# MB1280.net
KiCad netlist of a schematic drawn in Altium Designer
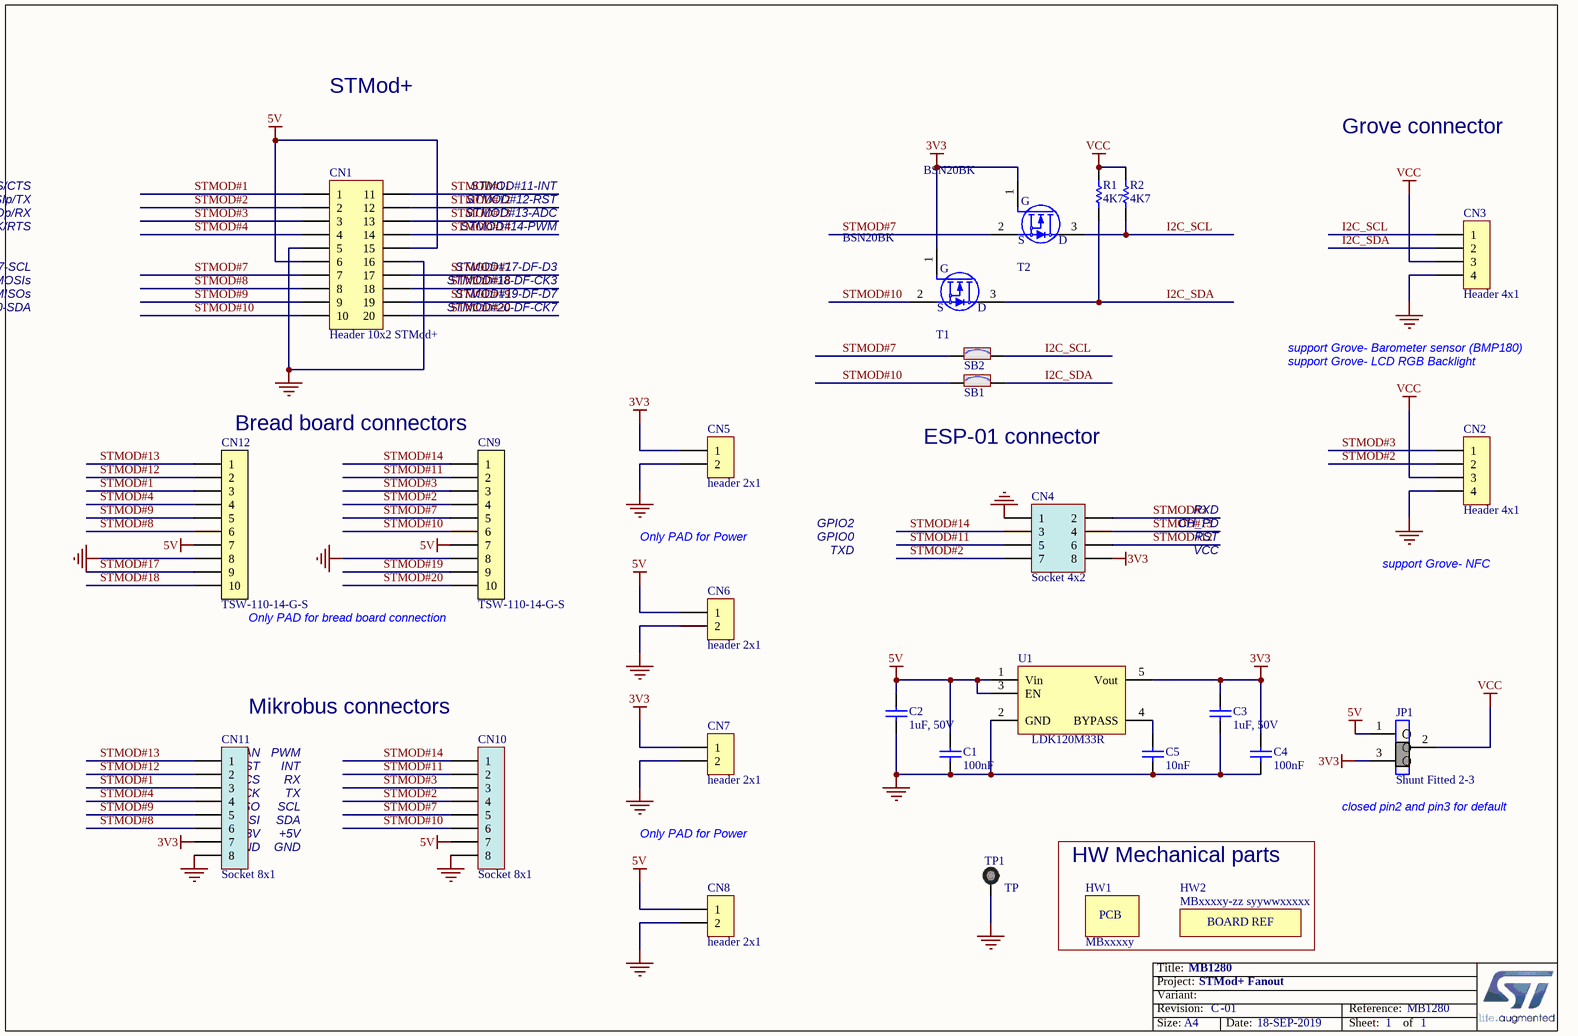
[diagram p0: MB1280.SchDoc]

(export (version "E")
  (design (tool "Eeschema 10.0.6"))
  (components
    (comp (ref "C1")
      (value "100nF")
      (footprint "C0603")
      (description "Capacitor, MLCC, 100nF, 16V, X7R, 10%, 0603, T=0,8mm")
      (fields
        (field (name "INTERNAL_PART_NUMBER") "MCD-00211")
        (field (name "MANUFACTURER_PART_NUMBER") "CC0603KRX7R7BB104")
        (field (name "PROVIDED_BY") "SUBCO")
      )
      (libsource (lib "MCD_PARTS_database") (part "Capacitor"))
    )
    (comp (ref "C2")
      (value "1uF, 50V")
      (footprint "C0603_H0P8")
      (description "Capacitor,1uF,50V,X5R,10%,0603, T=0.8mm")
      (fields
        (field (name "INTERNAL_PART_NUMBER") "MCD-01703")
        (field (name "MANUFACTURER_PART_NUMBER") "CC0603KRX5R9BB105")
        (field (name "PROVIDED_BY") "SUBCO")
      )
      (libsource (lib "MCD_PARTS_database") (part "Capacitor"))
    )
    (comp (ref "C3")
      (value "1uF, 50V")
      (footprint "C0603_H0P8")
      (description "Capacitor,1uF,50V,X5R,10%,0603, T=0.8mm")
      (fields
        (field (name "INTERNAL_PART_NUMBER") "MCD-01703")
        (field (name "MANUFACTURER_PART_NUMBER") "CC0603KRX5R9BB105")
        (field (name "PROVIDED_BY") "SUBCO")
      )
      (libsource (lib "MCD_PARTS_database") (part "Capacitor"))
    )
    (comp (ref "C4")
      (value "100nF")
      (footprint "C0603")
      (description "Capacitor, MLCC, 100nF, 16V, X7R, 10%, 0603, T=0,8mm")
      (fields
        (field (name "INTERNAL_PART_NUMBER") "MCD-00211")
        (field (name "MANUFACTURER_PART_NUMBER") "CC0603KRX7R7BB104")
        (field (name "PROVIDED_BY") "SUBCO")
      )
      (libsource (lib "MCD_PARTS_database") (part "Capacitor"))
    )
    (comp (ref "C5")
      (value "10nF")
      (footprint "C0603")
      (description "Capacitor, MLCC, 10nF, 50V, X7R, 10%, 0603, T=0.8mm")
      (fields
        (field (name "INTERNAL_PART_NUMBER") "MCD-00017")
        (field (name "MANUFACTURER_PART_NUMBER") "CC0603KRX7R9BB103")
        (field (name "PROVIDED_BY") "SUBCO")
      )
      (libsource (lib "MCD_PARTS_database") (part "Capacitor"))
    )
    (comp (ref "CN1")
      (value "Header 10x2 STMod+")
      (footprint "CON_SAMTEC_TMM-110-01-L-D-RA__STMOD+")
      (description "Header 10x2, 2mm, RA, TH, Height 3.20mm/3.50mm")
      (fields
        (field (name "INTERNAL_PART_NUMBER") "MCD-00288")
        (field (name "MANUFACTURER_PART_NUMBER") "TMM-110-01-L-D-RA")
        (field (name "PROVIDED_BY") "SUBCO")
      )
      (libsource (lib "MCD_PARTS_database") (part "Header 10x2 STMod+"))
    )
    (comp (ref "CN2")
      (value "Header 4x1")
      (footprint "CON_988-JIUBABA_A2006LF-04A")
      (description "Header 4x1, 2mm, VR, SMT")
      (fields
        (field (name "INTERNAL_PART_NUMBER") "MCD-01741")
        (field (name "MANUFACTURER_PART_NUMBER") "A2006LF-04A")
        (field (name "PROVIDED_BY") "SUBCO")
      )
      (libsource (lib "MCD_PARTS_database") (part "Header 4x1"))
    )
    (comp (ref "CN3")
      (value "Header 4x1")
      (footprint "CON_988-JIUBABA_A2006LF-04A")
      (description "Header 4x1, 2mm, VR, SMT")
      (fields
        (field (name "INTERNAL_PART_NUMBER") "MCD-01741")
        (field (name "MANUFACTURER_PART_NUMBER") "A2006LF-04A")
        (field (name "PROVIDED_BY") "SUBCO")
      )
      (libsource (lib "MCD_PARTS_database") (part "Header 4x1"))
    )
    (comp (ref "CN4")
      (value "Socket 4x2")
      (footprint "CON_SAMTEC_SSW-104-01-X-D")
      (description "Socket 4x2,2.54mm,VR,TH, height 8.51/2.64mm")
      (fields
        (field (name "INTERNAL_PART_NUMBER") "MCD-01742")
        (field (name "MANUFACTURER_PART_NUMBER") "SSW-104-01-G-D")
        (field (name "PROVIDED_BY") "SUBCO")
      )
      (libsource (lib "MCD_PARTS_database") (part "Socket 4x2"))
    )
    (comp (ref "CN5")
      (value "header 2x1")
      (footprint "CON_988-JIUBABA_PHFS25-11-02-G0B115-T-1")
      (description "Header, 2x1, 2.54mm, VR, TH, Height 6mm/3mm")
      (fields
        (field (name "INTERNAL_PART_NUMBER") "MCD-00314")
        (field (name "MANUFACTURER_PART_NUMBER") "PHFS25-11-02-G0B115-T-1")
        (field (name "PROVIDED_BY") "SUBCO")
      )
      (libsource (lib "MCD_PARTS_database") (part "Header 2x1"))
    )
    (comp (ref "CN6")
      (value "header 2x1")
      (footprint "CON_988-JIUBABA_PHFS25-11-02-G0B115-T-1")
      (description "Header, 2x1, 2.54mm, VR, TH, Height 6mm/3mm")
      (fields
        (field (name "INTERNAL_PART_NUMBER") "MCD-00314")
        (field (name "MANUFACTURER_PART_NUMBER") "PHFS25-11-02-G0B115-T-1")
        (field (name "PROVIDED_BY") "SUBCO")
      )
      (libsource (lib "MCD_PARTS_database") (part "Header 2x1"))
    )
    (comp (ref "CN7")
      (value "header 2x1")
      (footprint "CON_988-JIUBABA_PHFS25-11-02-G0B115-T-1")
      (description "Header, 2x1, 2.54mm, VR, TH, Height 6mm/3mm")
      (fields
        (field (name "INTERNAL_PART_NUMBER") "MCD-00314")
        (field (name "MANUFACTURER_PART_NUMBER") "PHFS25-11-02-G0B115-T-1")
        (field (name "PROVIDED_BY") "SUBCO")
      )
      (libsource (lib "MCD_PARTS_database") (part "Header 2x1"))
    )
    (comp (ref "CN8")
      (value "header 2x1")
      (footprint "CON_988-JIUBABA_PHFS25-11-02-G0B115-T-1")
      (description "Header, 2x1, 2.54mm, VR, TH, Height 6mm/3mm")
      (fields
        (field (name "INTERNAL_PART_NUMBER") "MCD-00314")
        (field (name "MANUFACTURER_PART_NUMBER") "PHFS25-11-02-G0B115-T-1")
        (field (name "PROVIDED_BY") "SUBCO")
      )
      (libsource (lib "MCD_PARTS_database") (part "Header 2x1"))
    )
    (comp (ref "CN9")
      (value "TSW-110-14-G-S")
      (footprint "CON_SAMTEC_TSW-110-14-G-S")
      (description "Header 10x1, 2,54mm height  10.67mm")
      (fields
        (field (name "INTERNAL_PART_NUMBER") "MCD-01591")
        (field (name "MANUFACTURER") "SAMTEC")
        (field (name "PROVIDED_BY") "SUBCO")
      )
      (libsource (lib "MCD_PARTS_database") (part "Header 10x1"))
    )
    (comp (ref "CN10")
      (value "Socket 8x1")
      (footprint "CON_SAMTEC_SSW-108-01-X-S")
      (description "Socket 8x1, 2.54mm, VR, TH, height 8.51/2.64mm")
      (fields
        (field (name "INTERNAL_PART_NUMBER") "MCD-01743")
        (field (name "MANUFACTURER_PART_NUMBER") "SSW-108-01-x-S")
        (field (name "PROVIDED_BY") "SUBCO")
      )
      (libsource (lib "MCD_PARTS_database") (part "Socket 8x1"))
    )
    (comp (ref "CN11")
      (value "Socket 8x1")
      (footprint "CON_SAMTEC_SSW-108-01-X-S")
      (description "Socket 8x1, 2.54mm, VR, TH, height 8.51/2.64mm")
      (fields
        (field (name "INTERNAL_PART_NUMBER") "MCD-01743")
        (field (name "MANUFACTURER_PART_NUMBER") "SSW-108-01-x-S")
        (field (name "PROVIDED_BY") "SUBCO")
      )
      (libsource (lib "MCD_PARTS_database") (part "Socket 8x1"))
    )
    (comp (ref "CN12")
      (value "TSW-110-14-G-S")
      (footprint "CON_SAMTEC_TSW-110-14-G-S")
      (description "Header 10x1, 2,54mm height  10.67mm")
      (fields
        (field (name "INTERNAL_PART_NUMBER") "MCD-01591")
        (field (name "MANUFACTURER") "SAMTEC")
        (field (name "PROVIDED_BY") "SUBCO")
      )
      (libsource (lib "MCD_PARTS_database") (part "Header 10x1"))
    )
    (comp (ref "HW1")
      (value "MBxxxxy")
      (description "PCB, xxxx for PCB number, Y for PCB revision")
      (fields
        (field (name "INTERNAL_PART_NUMBER") "MCD-00216")
        (field (name "MANUFACTURER_PART_NUMBER") "n/a")
        (field (name "PROVIDED_BY") "SUBCO")
      )
      (libsource (lib "MCD_PARTS_database") (part "PCB"))
    )
    (comp (ref "HW2")
      (value "MBxxxxy-zz syywwxxxxx")
      (footprint "STICKER_25X9")
      (description "Sticker to mention board reference + serial number")
      (fields
        (field (name "INTERNAL_PART_NUMBER") "MCD-00235")
        (field (name "MANUFACTURER_PART_NUMBER") "n/a")
        (field (name "PROVIDED_BY") "SUBCO")
      )
      (libsource (lib "MCD_PARTS_database") (part "STICKER_BOARD_REF"))
    )
    (comp (ref "JP1")
      (value "Shunt Fitted 2-3")
      (footprint "CON_SAMTEC_TSW-103-07-F-S")
      (description "Header, 3x1, 2,54mm, VR, TH, Height 5.84mm/2.54mm - Shunt Fitted 2-3 by default")
      (fields
        (field (name "INTERNAL_PART_NUMBER") "MCD-00685")
        (field (name "MANUFACTURER_PART_NUMBER") "TSW-103-07-F-S")
        (field (name "PROVIDED_BY") "SUBCO")
      )
      (libsource (lib "MCD_PARTS_database") (part "Jumper_Header 3x1 Fitted 2-3"))
    )
    (comp (ref "R1")
      (value "4K7")
      (footprint "R0603")
      (description "Resistor,4K7,0603,1%,1/10W")
      (fields
        (field (name "INTERNAL_PART_NUMBER") "MCD-00219")
        (field (name "MANUFACTURER_PART_NUMBER") "RC0603FR-074K7L")
        (field (name "PROVIDED_BY") "SUBCO")
      )
      (libsource (lib "MCD_PARTS_database") (part "Resistor"))
    )
    (comp (ref "R2")
      (value "4K7")
      (footprint "R0603")
      (description "Resistor,4K7,0603,1%,1/10W")
      (fields
        (field (name "INTERNAL_PART_NUMBER") "MCD-00219")
        (field (name "MANUFACTURER_PART_NUMBER") "RC0603FR-074K7L")
        (field (name "PROVIDED_BY") "SUBCO")
      )
      (libsource (lib "MCD_PARTS_database") (part "Resistor"))
    )
    (comp (ref "SB1")
      (value "SB_ON")
      (footprint "SOLDER-BRIDGE_R0603-0R")
      (description "Solder Bridge ON")
      (fields
        (field (name "INTERNAL_PART_NUMBER") "MCD-00071")
        (field (name "MANUFACTURER_PART_NUMBER") "RC0603JR-070RL")
        (field (name "PROVIDED_BY") "SUBCO")
      )
      (libsource (lib "MCD_PARTS_database") (part "SB_ON"))
    )
    (comp (ref "SB2")
      (value "SB_ON")
      (footprint "SOLDER-BRIDGE_R0603-0R")
      (description "Solder Bridge ON")
      (fields
        (field (name "INTERNAL_PART_NUMBER") "MCD-00071")
        (field (name "MANUFACTURER_PART_NUMBER") "RC0603JR-070RL")
        (field (name "PROVIDED_BY") "SUBCO")
      )
      (libsource (lib "MCD_PARTS_database") (part "SB_ON"))
    )
    (comp (ref "T1")
      (value "BSN20BK")
      (footprint "MOS_SOT23")
      (description "N-channel enhancement mode field-effect transistor")
      (fields
        (field (name "INTERNAL_PART_NUMBER") "MCD-01969")
        (field (name "MANUFACTURER") "Nexperia")
        (field (name "PROVIDED_BY") "SUBCO")
      )
      (libsource (lib "MCD_PARTS_database") (part "BSN20"))
    )
    (comp (ref "T2")
      (value "BSN20BK")
      (footprint "MOS_SOT23")
      (description "N-channel enhancement mode field-effect transistor")
      (fields
        (field (name "INTERNAL_PART_NUMBER") "MCD-01969")
        (field (name "MANUFACTURER") "Nexperia")
        (field (name "PROVIDED_BY") "SUBCO")
      )
      (libsource (lib "MCD_PARTS_database") (part "BSN20"))
    )
    (comp (ref "TP1")
      (value "TP")
      (footprint "TP_PTH_1MM_2MM")
      (description "Test Point trought hole 1mm/2mm")
      (fields
        (field (name "INTERNAL_PART_NUMBER") "MCD-01506")
        (field (name "Comment") "Test_Point_PTH_1mm_2mm")
      )
      (libsource (lib "MCD_PARTS_database") (part "Test_Point_PTH_1mm_2mm"))
    )
    (comp (ref "U1")
      (value "LDK120M33R")
      (footprint "REG_SOT23-5L")
      (description "200 mA low quiescent current very low noise LDO")
      (fields
        (field (name "INTERNAL_PART_NUMBER") "MCD-00663")
        (field (name "MANUFACTURER") "STMICROELECTRONICS")
        (field (name "PROVIDED_BY") "SUBCO with ST control")
      )
      (libsource (lib "MCD_PARTS_database") (part "LDK120M33R"))
    )
  )
  (nets
    (net (code "1") (name "/I2C_SCL") (class "Default")
      (node (ref "CN3") (pin "1") (pinfunction "1_1") (pintype "passive"))
      (node (ref "R2") (pin "2") (pinfunction "2_2") (pintype "passive"))
      (node (ref "SB2") (pin "2") (pinfunction "2_2") (pintype "passive"))
      (node (ref "T2") (pin "3") (pinfunction "D_3") (pintype "passive"))
    )
    (net (code "2") (name "/I2C_SDA") (class "Default")
      (node (ref "CN3") (pin "2") (pinfunction "2_2") (pintype "passive"))
      (node (ref "R1") (pin "2") (pinfunction "2_2") (pintype "passive"))
      (node (ref "SB1") (pin "2") (pinfunction "2_2") (pintype "passive"))
      (node (ref "T1") (pin "3") (pinfunction "D_3") (pintype "passive"))
    )
    (net (code "3") (name "/STMOD#1") (class "Default")
      (node (ref "CN1") (pin "1") (pinfunction "1_1") (pintype "passive"))
      (node (ref "CN11") (pin "3") (pinfunction "3_3") (pintype "passive"))
      (node (ref "CN12") (pin "3") (pinfunction "3_3") (pintype "passive"))
    )
    (net (code "4") (name "/STMOD#2") (class "Default")
      (node (ref "CN1") (pin "2") (pinfunction "2_2") (pintype "passive"))
      (node (ref "CN10") (pin "4") (pinfunction "4_4") (pintype "passive"))
      (node (ref "CN2") (pin "2") (pinfunction "2_2") (pintype "passive"))
      (node (ref "CN4") (pin "7") (pinfunction "7_7") (pintype "passive"))
      (node (ref "CN9") (pin "4") (pinfunction "4_4") (pintype "passive"))
    )
    (net (code "5") (name "/STMOD#3") (class "Default")
      (node (ref "CN1") (pin "3") (pinfunction "3_3") (pintype "passive"))
      (node (ref "CN10") (pin "3") (pinfunction "3_3") (pintype "passive"))
      (node (ref "CN2") (pin "1") (pinfunction "1_1") (pintype "passive"))
      (node (ref "CN4") (pin "2") (pinfunction "2_2") (pintype "passive"))
      (node (ref "CN9") (pin "3") (pinfunction "3_3") (pintype "passive"))
    )
    (net (code "6") (name "/STMOD#4") (class "Default")
      (node (ref "CN1") (pin "4") (pinfunction "4_4") (pintype "passive"))
      (node (ref "CN11") (pin "4") (pinfunction "4_4") (pintype "passive"))
      (node (ref "CN12") (pin "4") (pinfunction "4_4") (pintype "passive"))
    )
    (net (code "7") (name "/STMOD#7") (class "Default")
      (node (ref "CN1") (pin "7") (pinfunction "7_7") (pintype "passive"))
      (node (ref "CN10") (pin "5") (pinfunction "5_5") (pintype "passive"))
      (node (ref "CN9") (pin "5") (pinfunction "5_5") (pintype "passive"))
      (node (ref "SB2") (pin "1") (pinfunction "1_1") (pintype "passive"))
      (node (ref "T2") (pin "2") (pinfunction "S_2") (pintype "passive"))
    )
    (net (code "8") (name "/STMOD#8") (class "Default")
      (node (ref "CN1") (pin "8") (pinfunction "8_8") (pintype "passive"))
      (node (ref "CN11") (pin "6") (pinfunction "6_6") (pintype "passive"))
      (node (ref "CN12") (pin "6") (pinfunction "6_6") (pintype "passive"))
    )
    (net (code "9") (name "/STMOD#9") (class "Default")
      (node (ref "CN1") (pin "9") (pinfunction "9_9") (pintype "passive"))
      (node (ref "CN11") (pin "5") (pinfunction "5_5") (pintype "passive"))
      (node (ref "CN12") (pin "5") (pinfunction "5_5") (pintype "passive"))
    )
    (net (code "10") (name "/STMOD#10") (class "Default")
      (node (ref "CN1") (pin "10") (pinfunction "10_10") (pintype "passive"))
      (node (ref "CN10") (pin "6") (pinfunction "6_6") (pintype "passive"))
      (node (ref "CN9") (pin "6") (pinfunction "6_6") (pintype "passive"))
      (node (ref "SB1") (pin "1") (pinfunction "1_1") (pintype "passive"))
      (node (ref "T1") (pin "2") (pinfunction "S_2") (pintype "passive"))
    )
    (net (code "11") (name "/STMOD#11") (class "Default")
      (node (ref "CN1") (pin "11") (pinfunction "11_11") (pintype "passive"))
      (node (ref "CN10") (pin "2") (pinfunction "2_2") (pintype "passive"))
      (node (ref "CN4") (pin "5") (pinfunction "5_5") (pintype "passive"))
      (node (ref "CN9") (pin "2") (pinfunction "2_2") (pintype "passive"))
    )
    (net (code "12") (name "/STMOD#12") (class "Default")
      (node (ref "CN1") (pin "12") (pinfunction "12_12") (pintype "passive"))
      (node (ref "CN11") (pin "2") (pinfunction "2_2") (pintype "passive"))
      (node (ref "CN12") (pin "2") (pinfunction "2_2") (pintype "passive"))
      (node (ref "CN4") (pin "6") (pinfunction "6_6") (pintype "passive"))
    )
    (net (code "13") (name "/STMOD#13") (class "Default")
      (node (ref "CN1") (pin "13") (pinfunction "13_13") (pintype "passive"))
      (node (ref "CN11") (pin "1") (pinfunction "1_1") (pintype "passive"))
      (node (ref "CN12") (pin "1") (pinfunction "1_1") (pintype "passive"))
      (node (ref "CN4") (pin "4") (pinfunction "4_4") (pintype "passive"))
    )
    (net (code "14") (name "/STMOD#14") (class "Default")
      (node (ref "CN1") (pin "14") (pinfunction "14_14") (pintype "passive"))
      (node (ref "CN10") (pin "1") (pinfunction "1_1") (pintype "passive"))
      (node (ref "CN4") (pin "3") (pinfunction "3_3") (pintype "passive"))
      (node (ref "CN9") (pin "1") (pinfunction "1_1") (pintype "passive"))
    )
    (net (code "15") (name "/STMOD#17") (class "Default")
      (node (ref "CN1") (pin "17") (pinfunction "17_17") (pintype "passive"))
      (node (ref "CN12") (pin "9") (pinfunction "9_9") (pintype "passive"))
    )
    (net (code "16") (name "/STMOD#18") (class "Default")
      (node (ref "CN1") (pin "18") (pinfunction "18_18") (pintype "passive"))
      (node (ref "CN12") (pin "10") (pinfunction "10_10") (pintype "passive"))
    )
    (net (code "17") (name "/STMOD#19") (class "Default")
      (node (ref "CN1") (pin "19") (pinfunction "19_19") (pintype "passive"))
      (node (ref "CN9") (pin "9") (pinfunction "9_9") (pintype "passive"))
    )
    (net (code "18") (name "/STMOD#20") (class "Default")
      (node (ref "CN1") (pin "20") (pinfunction "20_20") (pintype "passive"))
      (node (ref "CN9") (pin "10") (pinfunction "10_10") (pintype "passive"))
    )
    (net (code "19") (name "3V3") (class "Default")
      (node (ref "C3") (pin "2") (pinfunction "2_2") (pintype "passive"))
      (node (ref "C4") (pin "2") (pinfunction "2_2") (pintype "passive"))
      (node (ref "CN11") (pin "7") (pinfunction "7_7") (pintype "passive"))
      (node (ref "CN4") (pin "8") (pinfunction "8_8") (pintype "passive"))
      (node (ref "CN5") (pin "1") (pinfunction "1_1") (pintype "passive"))
      (node (ref "CN7") (pin "1") (pinfunction "1_1") (pintype "passive"))
      (node (ref "JP1") (pin "3") (pinfunction "3_3") (pintype "passive"))
      (node (ref "T1") (pin "1") (pinfunction "G_1") (pintype "passive"))
      (node (ref "T2") (pin "1") (pinfunction "G_1") (pintype "passive"))
      (node (ref "U1") (pin "5") (pinfunction "Vout_5") (pintype "power_in"))
    )
    (net (code "20") (name "5V") (class "Default")
      (node (ref "C1") (pin "2") (pinfunction "2_2") (pintype "passive"))
      (node (ref "C2") (pin "2") (pinfunction "2_2") (pintype "passive"))
      (node (ref "CN1") (pin "15") (pinfunction "15_15") (pintype "passive"))
      (node (ref "CN1") (pin "6") (pinfunction "6_6") (pintype "passive"))
      (node (ref "CN10") (pin "7") (pinfunction "7_7") (pintype "passive"))
      (node (ref "CN12") (pin "7") (pinfunction "7_7") (pintype "passive"))
      (node (ref "CN6") (pin "1") (pinfunction "1_1") (pintype "passive"))
      (node (ref "CN8") (pin "1") (pinfunction "1_1") (pintype "passive"))
      (node (ref "CN9") (pin "7") (pinfunction "7_7") (pintype "passive"))
      (node (ref "JP1") (pin "1") (pinfunction "1_1") (pintype "passive"))
      (node (ref "U1") (pin "1") (pinfunction "Vin_1") (pintype "power_in"))
      (node (ref "U1") (pin "3") (pinfunction "EN_3") (pintype "passive"))
    )
    (net (code "21") (name "GND") (class "Default")
      (node (ref "C1") (pin "1") (pinfunction "1_1") (pintype "passive"))
      (node (ref "C2") (pin "1") (pinfunction "1_1") (pintype "passive"))
      (node (ref "C3") (pin "1") (pinfunction "1_1") (pintype "passive"))
      (node (ref "C4") (pin "1") (pinfunction "1_1") (pintype "passive"))
      (node (ref "C5") (pin "1") (pinfunction "1_1") (pintype "passive"))
      (node (ref "CN1") (pin "16") (pinfunction "16_16") (pintype "passive"))
      (node (ref "CN1") (pin "5") (pinfunction "5_5") (pintype "passive"))
      (node (ref "CN10") (pin "8") (pinfunction "8_8") (pintype "passive"))
      (node (ref "CN11") (pin "8") (pinfunction "8_8") (pintype "passive"))
      (node (ref "CN12") (pin "8") (pinfunction "8_8") (pintype "passive"))
      (node (ref "CN2") (pin "4") (pinfunction "4_4") (pintype "passive"))
      (node (ref "CN3") (pin "4") (pinfunction "4_4") (pintype "passive"))
      (node (ref "CN4") (pin "1") (pinfunction "1_1") (pintype "passive"))
      (node (ref "CN5") (pin "2") (pinfunction "2_2") (pintype "passive"))
      (node (ref "CN6") (pin "2") (pinfunction "2_2") (pintype "passive"))
      (node (ref "CN7") (pin "2") (pinfunction "2_2") (pintype "passive"))
      (node (ref "CN8") (pin "2") (pinfunction "2_2") (pintype "passive"))
      (node (ref "CN9") (pin "8") (pinfunction "8_8") (pintype "passive"))
      (node (ref "TP1") (pin "1") (pinfunction "1_1") (pintype "passive"))
      (node (ref "U1") (pin "2") (pinfunction "GND_2") (pintype "passive"))
    )
    (net (code "22") (name "Net-(U1-BYPASS)") (class "Default")
      (node (ref "C5") (pin "2") (pinfunction "2_2") (pintype "passive"))
      (node (ref "U1") (pin "4") (pinfunction "BYPASS_4") (pintype "passive"))
    )
    (net (code "23") (name "VCC") (class "Default")
      (node (ref "CN2") (pin "3") (pinfunction "3_3") (pintype "passive"))
      (node (ref "CN3") (pin "3") (pinfunction "3_3") (pintype "passive"))
      (node (ref "JP1") (pin "2") (pinfunction "2_2") (pintype "passive"))
      (node (ref "R1") (pin "1") (pinfunction "1_1") (pintype "passive"))
      (node (ref "R2") (pin "1") (pinfunction "1_1") (pintype "passive"))
    )
  )
)
